# 3pin-breakout.net
KiCad netlist of a schematic drawn in EAGLE
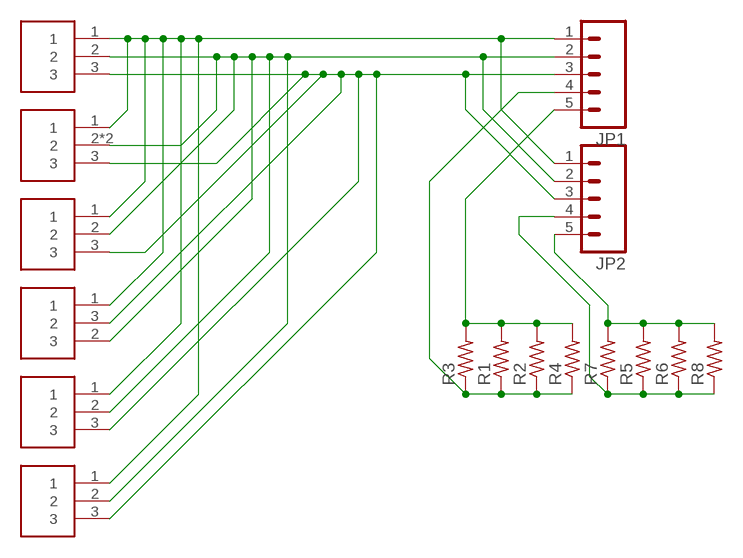
[diagram p0: schematic, sheet 1]

(export (version "E")
  (design (tool "Eeschema 10.0.6"))
  (components
    (comp (ref "JP1")
      (value "M05PTH")
      (footprint "eagle-import:1X05")
      (libsource (lib "eagle-import") (part "M05PTH"))
    )
    (comp (ref "JP2")
      (value "M05PTH")
      (footprint "eagle-import:1X05")
      (libsource (lib "eagle-import") (part "M05PTH"))
    )
    (comp (ref "R1")
      (value "RESISTORR0805")
      (footprint "eagle-import:R0805")
      (libsource (lib "eagle-import") (part "RESISTORR0805"))
    )
    (comp (ref "R2")
      (value "RESISTORR1206")
      (footprint "eagle-import:R1206")
      (libsource (lib "eagle-import") (part "RESISTORR1206"))
    )
    (comp (ref "R3")
      (value "RESISTORR0805")
      (footprint "eagle-import:R0805")
      (libsource (lib "eagle-import") (part "RESISTORR0805"))
    )
    (comp (ref "R4")
      (value "RESISTORR1206")
      (footprint "eagle-import:R1206")
      (libsource (lib "eagle-import") (part "RESISTORR1206"))
    )
    (comp (ref "R5")
      (value "RESISTORR0805")
      (footprint "eagle-import:R0805")
      (libsource (lib "eagle-import") (part "RESISTORR0805"))
    )
    (comp (ref "R6")
      (value "RESISTORR1206")
      (footprint "eagle-import:R1206")
      (libsource (lib "eagle-import") (part "RESISTORR1206"))
    )
    (comp (ref "R7")
      (value "RESISTORR0805")
      (footprint "eagle-import:R0805")
      (libsource (lib "eagle-import") (part "RESISTORR0805"))
    )
    (comp (ref "R8")
      (value "RESISTORR1206")
      (footprint "eagle-import:R1206")
      (libsource (lib "eagle-import") (part "RESISTORR1206"))
    )
    (comp (ref "U$1")
      (value "BLANK-3PINSOT23")
      (footprint "eagle-import:SOT-23")
      (libsource (lib "eagle-import") (part "BLANK-3PINSOT23"))
    )
    (comp (ref "U$2")
      (value "BLANK-3PINSOT223")
      (footprint "eagle-import:SOT-223")
      (libsource (lib "eagle-import") (part "BLANK-3PINSOT223"))
    )
    (comp (ref "U$3")
      (value "BLANK-3PINSOT323")
      (footprint "eagle-import:SC70")
      (libsource (lib "eagle-import") (part "BLANK-3PINSOT323"))
    )
    (comp (ref "U$4")
      (value "BLANK-3PINSOT416")
      (footprint "eagle-import:SC75_INFINEON")
      (libsource (lib "eagle-import") (part "BLANK-3PINSOT416"))
    )
    (comp (ref "U$5")
      (value "BLANK-3PINTO252")
      (footprint "eagle-import:TO252")
      (libsource (lib "eagle-import") (part "BLANK-3PINTO252"))
    )
    (comp (ref "U$6")
      (value "BLANK-3PINTO263")
      (footprint "eagle-import:TO263")
      (libsource (lib "eagle-import") (part "BLANK-3PINTO263"))
    )
  )
  (nets
    (net (code "1") (name "Net-(JP1-Pad1)") (class "Default")
      (node (ref "JP1") (pin "1") (pinfunction "1_1") (pintype "passive"))
      (node (ref "JP2") (pin "1") (pinfunction "1_1") (pintype "passive"))
      (node (ref "U$1") (pin "1") (pinfunction "1_1") (pintype "bidirectional"))
      (node (ref "U$2") (pin "1") (pinfunction "1_1") (pintype "bidirectional"))
      (node (ref "U$3") (pin "1") (pinfunction "1_1") (pintype "bidirectional"))
      (node (ref "U$4") (pin "1") (pinfunction "1_1") (pintype "bidirectional"))
      (node (ref "U$5") (pin "1") (pinfunction "1_1") (pintype "bidirectional"))
      (node (ref "U$6") (pin "1") (pinfunction "1_1") (pintype "bidirectional"))
    )
    (net (code "2") (name "Net-(JP1-Pad4)") (class "Default")
      (node (ref "JP1") (pin "4") (pinfunction "4_4") (pintype "passive"))
      (node (ref "R1") (pin "1") (pinfunction "1_1") (pintype "passive"))
      (node (ref "R2") (pin "1") (pinfunction "1_1") (pintype "passive"))
      (node (ref "R3") (pin "1") (pinfunction "1_1") (pintype "passive"))
      (node (ref "R4") (pin "1") (pinfunction "1_1") (pintype "passive"))
    )
    (net (code "3") (name "Net-(JP1-Pad5)") (class "Default")
      (node (ref "JP1") (pin "5") (pinfunction "5_5") (pintype "passive"))
      (node (ref "R1") (pin "2") (pinfunction "2_2") (pintype "passive"))
      (node (ref "R2") (pin "2") (pinfunction "2_2") (pintype "passive"))
      (node (ref "R3") (pin "2") (pinfunction "2_2") (pintype "passive"))
      (node (ref "R4") (pin "2") (pinfunction "2_2") (pintype "passive"))
    )
    (net (code "4") (name "Net-(JP2-Pad4)") (class "Default")
      (node (ref "JP2") (pin "4") (pinfunction "4_4") (pintype "passive"))
      (node (ref "R5") (pin "1") (pinfunction "1_1") (pintype "passive"))
      (node (ref "R6") (pin "1") (pinfunction "1_1") (pintype "passive"))
      (node (ref "R7") (pin "1") (pinfunction "1_1") (pintype "passive"))
      (node (ref "R8") (pin "1") (pinfunction "1_1") (pintype "passive"))
    )
    (net (code "5") (name "Net-(JP2-Pad5)") (class "Default")
      (node (ref "JP2") (pin "5") (pinfunction "5_5") (pintype "passive"))
      (node (ref "R5") (pin "2") (pinfunction "2_2") (pintype "passive"))
      (node (ref "R6") (pin "2") (pinfunction "2_2") (pintype "passive"))
      (node (ref "R7") (pin "2") (pinfunction "2_2") (pintype "passive"))
      (node (ref "R8") (pin "2") (pinfunction "2_2") (pintype "passive"))
    )
    (net (code "6") (name "Net-(U$4-2)") (class "Default")
      (node (ref "JP1") (pin "3") (pinfunction "3_3") (pintype "passive"))
      (node (ref "JP2") (pin "3") (pinfunction "3_3") (pintype "passive"))
      (node (ref "U$1") (pin "3") (pinfunction "3_3") (pintype "bidirectional"))
      (node (ref "U$2") (pin "3") (pinfunction "3_3") (pintype "bidirectional"))
      (node (ref "U$3") (pin "3") (pinfunction "3_3") (pintype "bidirectional"))
      (node (ref "U$4") (pin "3") (pinfunction "2_3") (pintype "bidirectional"))
      (node (ref "U$5") (pin "3") (pinfunction "3_3") (pintype "bidirectional"))
      (node (ref "U$6") (pin "3") (pinfunction "3_3") (pintype "bidirectional"))
    )
    (net (code "7") (name "Net-(U$4-3)") (class "Default")
      (node (ref "JP1") (pin "2") (pinfunction "2_2") (pintype "passive"))
      (node (ref "JP2") (pin "2") (pinfunction "2_2") (pintype "passive"))
      (node (ref "U$1") (pin "2") (pinfunction "2_2") (pintype "bidirectional"))
      (node (ref "U$2") (pin "2") (pinfunction "2_2") (pintype "bidirectional"))
      (node (ref "U$2") (pin "4") (pinfunction "2_4") (pintype "bidirectional"))
      (node (ref "U$3") (pin "2") (pinfunction "2_2") (pintype "bidirectional"))
      (node (ref "U$4") (pin "2") (pinfunction "3_2") (pintype "bidirectional"))
      (node (ref "U$5") (pin "2") (pinfunction "2_2") (pintype "bidirectional"))
      (node (ref "U$6") (pin "2") (pinfunction "2_2") (pintype "bidirectional"))
    )
  )
)
